# MPL3115A2.net
KiCad netlist of a schematic drawn in Altium Designer
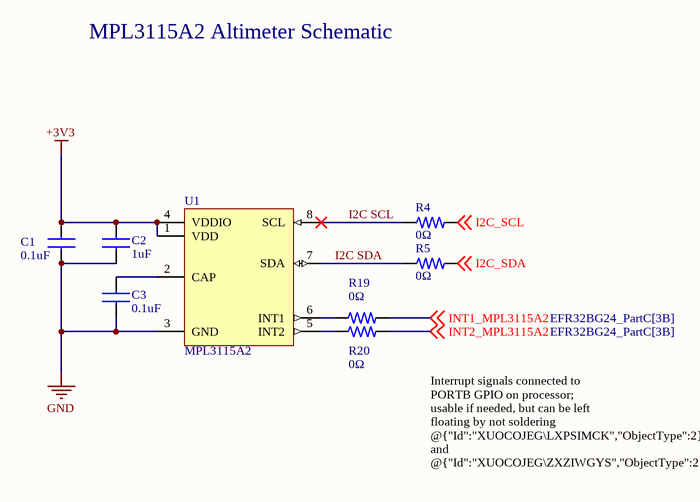
[diagram p0: MPL3115A2.SchDoc]

(export (version "E")
  (design (tool "Eeschema 10.0.6"))
  (components
    (comp (ref "C1")
      (value "0.1uF")
      (footprint "C_0603")
      (description "CAP CER 0.1UF 10V X5R 0603")
      (fields
        (field (name "MANUFACTURER") "KEMET")
        (field (name "MANUFACTURER PART NUMBER") "C0603C104K8PAC7867")
      )
      (libsource (lib "LPEDT_Parts") (part "C_0.1U_0603"))
    )
    (comp (ref "C2")
      (value "1uF")
      (footprint "C_0603")
      (description "CAP CER 1UF 10V X5R 0603")
      (fields
        (field (name "MANUFACTURER") "Murata")
        (field (name "MANUFACTURER PART NUMBER") "GRM188R61A105KA61D")
      )
      (libsource (lib "LPEDT_Parts") (part "C_1U_0603"))
    )
    (comp (ref "C3")
      (value "0.1uF")
      (footprint "C_0603")
      (description "CAP CER 0.1UF 10V X5R 0603")
      (fields
        (field (name "MANUFACTURER") "KEMET")
        (field (name "MANUFACTURER PART NUMBER") "C0603C104K8PAC7867")
      )
      (libsource (lib "LPEDT_Parts") (part "C_0.1U_0603"))
    )
    (comp (ref "R4")
      (value "0Ω")
      (footprint "R_0603")
      (description "RES 0OHM 0.1W 0603")
      (fields
        (field (name "MANUFACTURER") "Stackpole Electronics")
        (field (name "MANUFACTURER PART NUMBER") "RMCF0603ZT0R00")
      )
      (libsource (lib "LPEDT_Parts") (part "R_0_0603"))
    )
    (comp (ref "R5")
      (value "0Ω")
      (footprint "R_0603")
      (description "RES 0OHM 0.1W 0603")
      (fields
        (field (name "MANUFACTURER") "Stackpole Electronics")
        (field (name "MANUFACTURER PART NUMBER") "RMCF0603ZT0R00")
      )
      (libsource (lib "LPEDT_Parts") (part "R_0_0603"))
    )
    (comp (ref "R19")
      (value "0Ω")
      (footprint "R_0603")
      (description "RES 0OHM 0.1W 0603")
      (fields
        (field (name "MANUFACTURER") "Stackpole Electronics")
        (field (name "MANUFACTURER PART NUMBER") "RMCF0603ZT0R00")
      )
      (libsource (lib "LPEDT_Parts") (part "R_0_0603"))
    )
    (comp (ref "R20")
      (value "0Ω")
      (footprint "R_0603")
      (description "RES 0OHM 0.1W 0603")
      (fields
        (field (name "MANUFACTURER") "Stackpole Electronics")
        (field (name "MANUFACTURER PART NUMBER") "RMCF0603ZT0R00")
      )
      (libsource (lib "LPEDT_Parts") (part "R_0_0603"))
    )
    (comp (ref "U1")
      (value "MPL3115A2")
      (footprint "U_MPL3115A2")
      (description "Pressure Sensor 7.25PSI ~ 15.95PSI (50kPa ~ 110kPa) Absolute 24 b 8-TLGA")
      (libsource (lib "LPEDT_Parts") (part "U_MPL3115A2"))
    )
  )
  (nets
    (net (code "1") (name "+3V3") (class "Default")
      (node (ref "C1") (pin "1") (pinfunction "1_1") (pintype "passive"))
      (node (ref "C2") (pin "2") (pinfunction "2_2") (pintype "passive"))
      (node (ref "U1") (pin "1") (pinfunction "VDD_1") (pintype "power_in"))
      (node (ref "U1") (pin "4") (pinfunction "VDDIO_4") (pintype "power_in"))
    )
    (net (code "2") (name "/I2C SCL") (class "Default")
      (node (ref "R4") (pin "1") (pinfunction "1_1") (pintype "passive"))
      (node (ref "U1") (pin "8") (pinfunction "SCL_8") (pintype "input"))
    )
    (net (code "3") (name "/I2C SDA") (class "Default")
      (node (ref "R5") (pin "1") (pinfunction "1_1") (pintype "passive"))
      (node (ref "U1") (pin "7") (pinfunction "SDA_7") (pintype "bidirectional"))
    )
    (net (code "4") (name "GND") (class "Default")
      (node (ref "C1") (pin "2") (pinfunction "2_2") (pintype "passive"))
      (node (ref "C2") (pin "1") (pinfunction "1_1") (pintype "passive"))
      (node (ref "C3") (pin "2") (pinfunction "2_2") (pintype "passive"))
      (node (ref "U1") (pin "3") (pinfunction "GND_3") (pintype "power_in"))
    )
    (net (code "5") (name "I2C_SCL") (class "Default")
      (node (ref "R4") (pin "2") (pinfunction "2_2") (pintype "passive"))
    )
    (net (code "6") (name "I2C_SDA") (class "Default")
      (node (ref "R5") (pin "2") (pinfunction "2_2") (pintype "passive"))
    )
    (net (code "7") (name "INT1_MPL3115A2") (class "Default")
      (node (ref "R19") (pin "2") (pinfunction "2_2") (pintype "passive"))
    )
    (net (code "8") (name "INT2_MPL3115A2") (class "Default")
      (node (ref "R20") (pin "2") (pinfunction "2_2") (pintype "passive"))
    )
    (net (code "9") (name "Net-(U1-CAP)") (class "Default")
      (node (ref "C3") (pin "1") (pinfunction "1_1") (pintype "passive"))
      (node (ref "U1") (pin "2") (pinfunction "CAP_2") (pintype "power_in"))
    )
    (net (code "10") (name "Net-(U1-INT1)") (class "Default")
      (node (ref "R19") (pin "1") (pinfunction "1_1") (pintype "passive"))
      (node (ref "U1") (pin "6") (pinfunction "INT1_6") (pintype "output"))
    )
    (net (code "11") (name "Net-(U1-INT2)") (class "Default")
      (node (ref "R20") (pin "1") (pinfunction "1_1") (pintype "passive"))
      (node (ref "U1") (pin "5") (pinfunction "INT2_5") (pintype "output"))
    )
  )
)
